# 02-USB3.net
KiCad netlist of a schematic drawn in Altium Designer
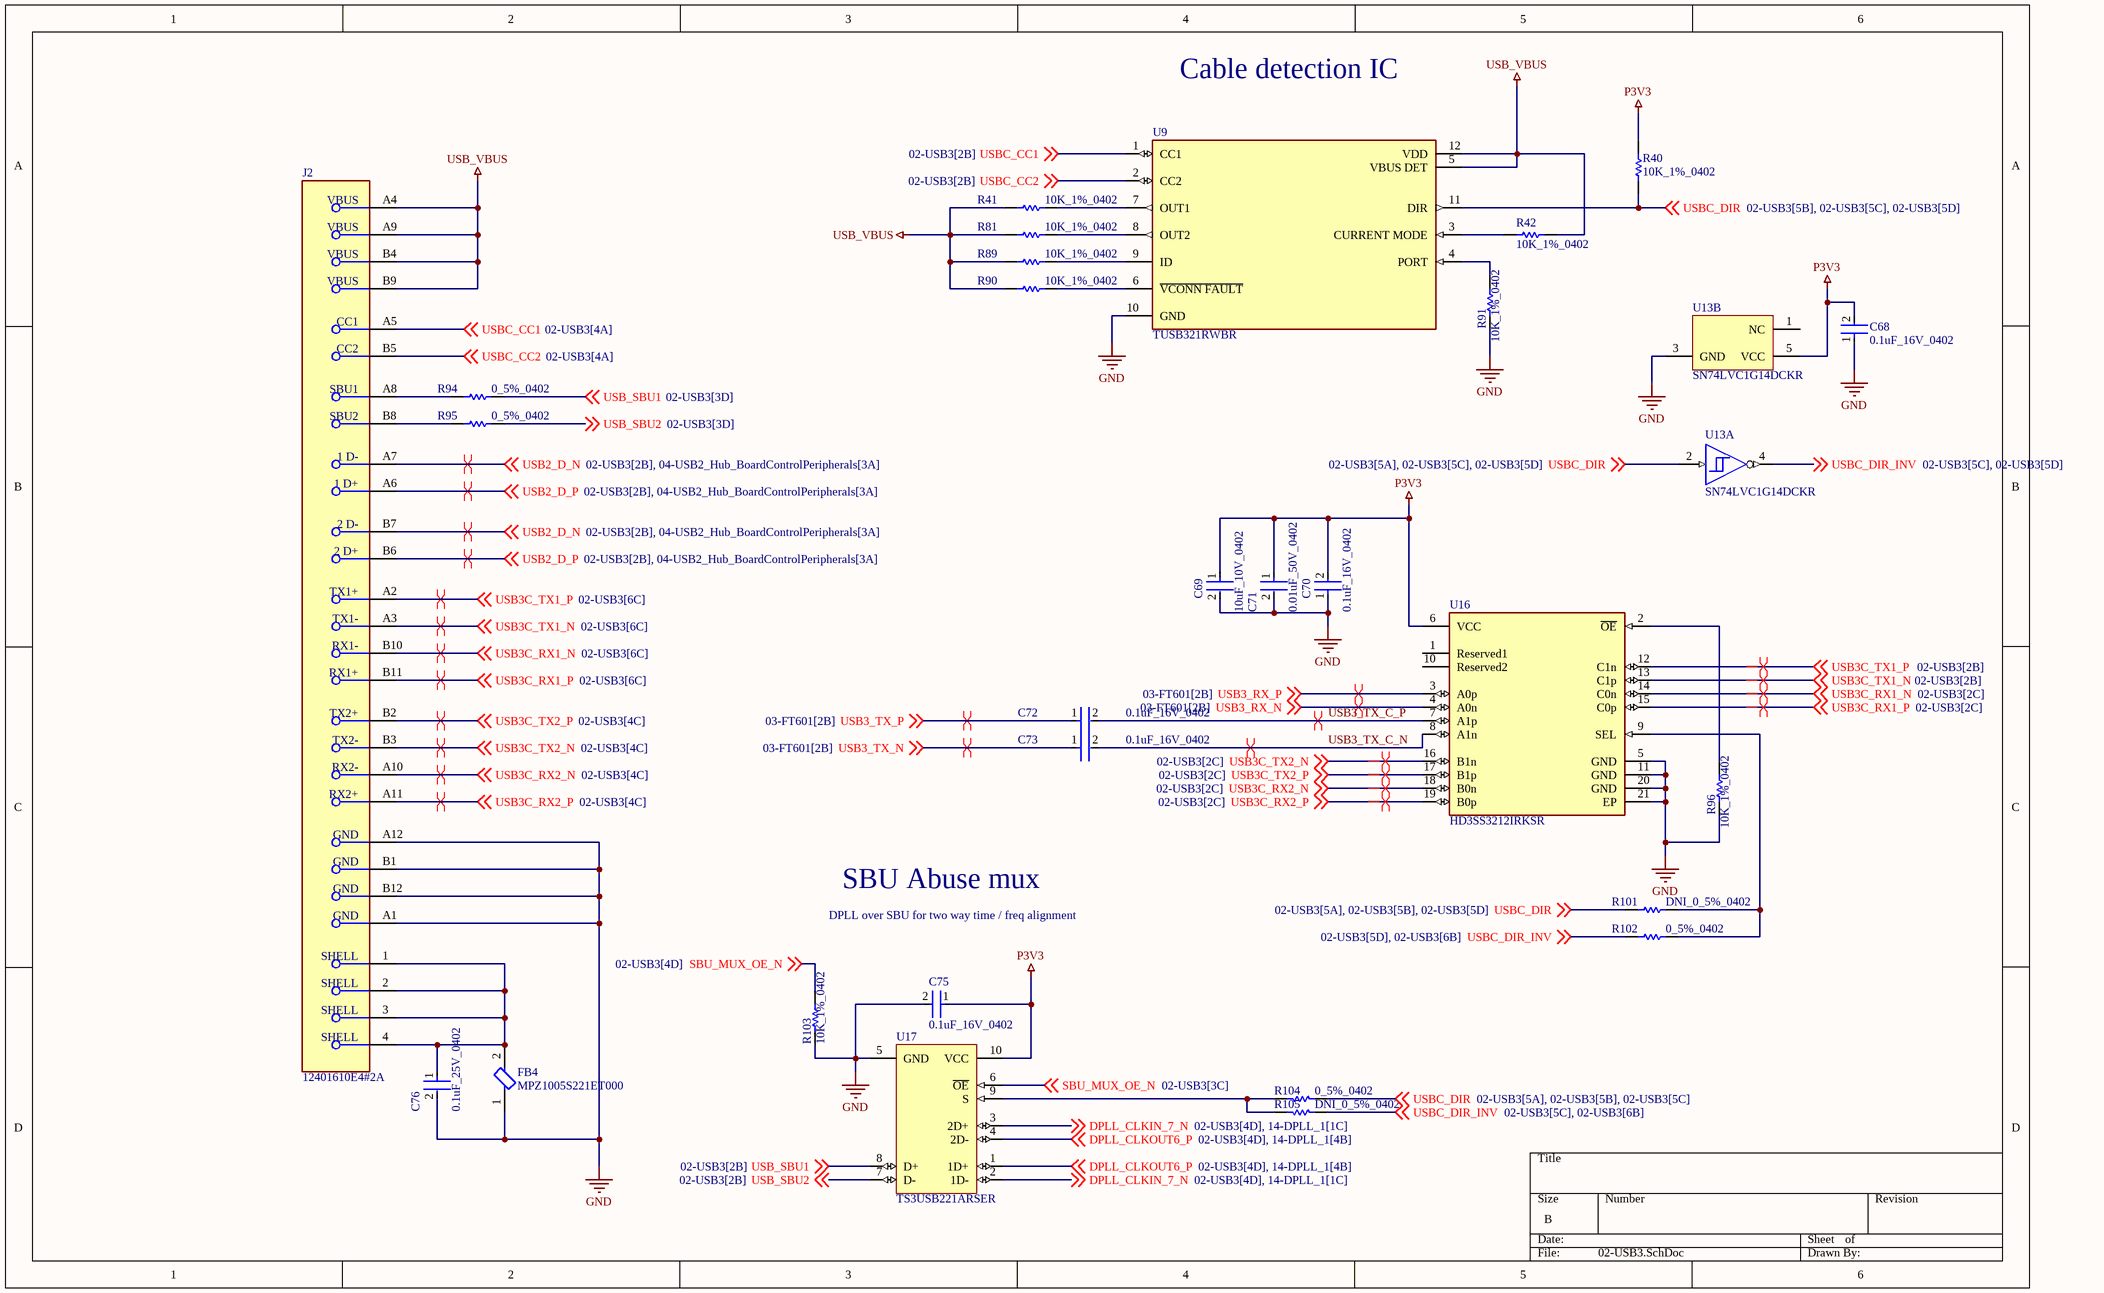
[diagram p0: 02-USB3.SchDoc]

(export (version "E")
  (design (tool "Eeschema 10.0.6"))
  (components
    (comp (ref "C68")
      (value "0.1uF_16V_0402")
      (footprint "FP-C0402-BB-MFG")
      (description "CAP CER 0.1UF 16V 5% X7R 0402")
      (fields
        (field (name "MANUFACTURER") "Kemet")
        (field (name "MANUFACTURER PART NUMBER") "C0402C104J4RACTU")
      )
      (libsource (lib "Altium Content Vault") (part "b4654b650e69147ec39a6b967a45e02"))
    )
    (comp (ref "C69")
      (value "10uF_10V_0402")
      (footprint "FP-CL05A106MP5NUNC-MFG")
      (description "CAP CER 10UF 10V X5R 0402")
      (fields
        (field (name "OCTOPART") "https://octopart.com/cl05a106mp5nunc-samsung-22457395")
        (field (name "TOLERANCE") "20%")
      )
      (libsource (lib "Altium Content Vault") (part "b4654b650e69147ec39a6b967a45e02"))
    )
    (comp (ref "C70")
      (value "0.1uF_16V_0402")
      (footprint "FP-C0402-BB-MFG")
      (description "CAP CER 0.1UF 16V 5% X7R 0402")
      (fields
        (field (name "MANUFACTURER") "Kemet")
        (field (name "MANUFACTURER PART NUMBER") "C0402C104J4RACTU")
      )
      (libsource (lib "Altium Content Vault") (part "b4654b650e69147ec39a6b967a45e02"))
    )
    (comp (ref "C71")
      (value "0.01uF_50V_0402")
      (footprint "FP-C0402-BB-MFG")
      (description "CAP CER 10000PF 50V X7R 0402")
      (fields (field (name "TOLERANCE") "0.1") (field (name "MANUFACTURER") "Kemet"))
      (libsource (lib "Altium Content Vault") (part "b4654b650e69147ec39a6b967a45e02"))
    )
    (comp (ref "C72")
      (value "0.1uF_16V_0402")
      (footprint "FP-C0402-BB-MFG")
      (description "CAP CER 0.1UF 16V 5% X7R 0402")
      (fields
        (field (name "MANUFACTURER") "Kemet")
        (field (name "MANUFACTURER PART NUMBER") "C0402C104J4RACTU")
      )
      (libsource (lib "Altium Content Vault") (part "b4654b650e69147ec39a6b967a45e02"))
    )
    (comp (ref "C73")
      (value "0.1uF_16V_0402")
      (footprint "FP-C0402-BB-MFG")
      (description "CAP CER 0.1UF 16V 5% X7R 0402")
      (fields
        (field (name "MANUFACTURER") "Kemet")
        (field (name "MANUFACTURER PART NUMBER") "C0402C104J4RACTU")
      )
      (libsource (lib "Altium Content Vault") (part "b4654b650e69147ec39a6b967a45e02"))
    )
    (comp (ref "C75")
      (value "0.1uF_16V_0402")
      (footprint "FP-C0402-BB-MFG")
      (description "CAP CER 0.1UF 16V 5% X7R 0402")
      (fields
        (field (name "MANUFACTURER") "Kemet")
        (field (name "MANUFACTURER PART NUMBER") "C0402C104J4RACTU")
      )
      (libsource (lib "Altium Content Vault") (part "b4654b650e69147ec39a6b967a45e02"))
    )
    (comp (ref "C76")
      (value "0.1uF_25V_0402")
      (footprint "FP-CGA2B-IPC_B")
      (description "Cap Ceramic 100nF 25V X7R 10% Pad SMD 0402 +125°C Automotive T/R")
      (fields (field (name "VOLTAGE") "25V") (field (name "TOLERANCE") "10%"))
      (libsource (lib "Altium Content Vault") (part "b4654b650e69147ec39a6b967a45e02"))
    )
    (comp (ref "FB4")
      (value "MPZ1005S221ET000")
      (footprint "FP-MPZ1005-IPC_A")
      (description "Power line Ferrite Bead 220Ω @ 100MHz 0.9A DCR 0.22Ω SMD 0402")
      (fields (field (name "TOLERANCE") "25%"))
      (libsource (lib "Altium Content Vault") (part "5f30dd21d616792df468990f7003faa"))
    )
    (comp (ref "J2")
      (value "12401610E4#2A")
      (footprint "FP-12401610E4#2A-MFG")
      (description "CONN RCP USB3.1 TYPEC 24P SMD RA")
      (libsource (lib "Altium Content Vault") (part "7c76f4c47d7e2af8b8797da79635f2a"))
    )
    (comp (ref "R40")
      (value "10K_1%_0402")
      (footprint "RESC1005X40X25NL10T10")
      (fields (field (name "MANUFACTURER") "Bourns") (field (name "PART NUMBER") "CR0402-FX-1002GLF"))
      (libsource (lib "Altium Content Vault") (part "RES"))
    )
    (comp (ref "R41")
      (value "10K_1%_0402")
      (footprint "RESC1005X40X25NL10T10")
      (fields (field (name "MANUFACTURER") "Bourns") (field (name "PART NUMBER") "CR0402-FX-1002GLF"))
      (libsource (lib "Altium Content Vault") (part "RES"))
    )
    (comp (ref "R42")
      (value "10K_1%_0402")
      (footprint "RESC1005X40X25NL10T10")
      (fields (field (name "MANUFACTURER") "Bourns") (field (name "PART NUMBER") "CR0402-FX-1002GLF"))
      (libsource (lib "Altium Content Vault") (part "RES"))
    )
    (comp (ref "R81")
      (value "10K_1%_0402")
      (footprint "RESC1005X40X25NL10T10")
      (fields (field (name "MANUFACTURER") "Bourns") (field (name "PART NUMBER") "CR0402-FX-1002GLF"))
      (libsource (lib "Altium Content Vault") (part "RES"))
    )
    (comp (ref "R89")
      (value "10K_1%_0402")
      (footprint "RESC1005X40X25NL10T10")
      (fields (field (name "MANUFACTURER") "Bourns") (field (name "PART NUMBER") "CR0402-FX-1002GLF"))
      (libsource (lib "Altium Content Vault") (part "RES"))
    )
    (comp (ref "R90")
      (value "10K_1%_0402")
      (footprint "RESC1005X40X25NL10T10")
      (fields (field (name "MANUFACTURER") "Bourns") (field (name "PART NUMBER") "CR0402-FX-1002GLF"))
      (libsource (lib "Altium Content Vault") (part "RES"))
    )
    (comp (ref "R91")
      (value "10K_1%_0402")
      (footprint "RESC1005X40X25NL10T10")
      (fields (field (name "MANUFACTURER") "Bourns") (field (name "PART NUMBER") "CR0402-FX-1002GLF"))
      (libsource (lib "Altium Content Vault") (part "RES"))
    )
    (comp (ref "R94")
      (value "0_5%_0402")
      (footprint "RESC1005X40X25NL05T10")
      (fields (field (name "MANUFACTURER") "Panasonic") (field (name "PART NUMBER") "ERJ-U020R00X"))
      (libsource (lib "Altium Content Vault") (part "RES"))
    )
    (comp (ref "R95")
      (value "0_5%_0402")
      (footprint "RESC1005X40X25NL05T10")
      (fields (field (name "MANUFACTURER") "Panasonic") (field (name "PART NUMBER") "ERJ-U020R00X"))
      (libsource (lib "Altium Content Vault") (part "RES"))
    )
    (comp (ref "R96")
      (value "10K_1%_0402")
      (footprint "RESC1005X40X25NL10T10")
      (fields (field (name "MANUFACTURER") "Bourns") (field (name "PART NUMBER") "CR0402-FX-1002GLF"))
      (libsource (lib "Altium Content Vault") (part "RES"))
    )
    (comp (ref "R101")
      (value "DNI_0_5%_0402")
      (footprint "RESC1005X40X25NL05T10")
      (fields (field (name "MANUFACTURER") "Panasonic") (field (name "PART NUMBER") "ERJ-U020R00X"))
      (libsource (lib "Altium Content Vault") (part "RES"))
    )
    (comp (ref "R102")
      (value "0_5%_0402")
      (footprint "RESC1005X40X25NL05T10")
      (fields (field (name "MANUFACTURER") "Panasonic") (field (name "PART NUMBER") "ERJ-U020R00X"))
      (libsource (lib "Altium Content Vault") (part "RES"))
    )
    (comp (ref "R103")
      (value "10K_1%_0402")
      (footprint "RESC1005X40X25NL10T10")
      (fields (field (name "MANUFACTURER") "Bourns") (field (name "PART NUMBER") "CR0402-FX-1002GLF"))
      (libsource (lib "Altium Content Vault") (part "RES"))
    )
    (comp (ref "R104")
      (value "0_5%_0402")
      (footprint "RESC1005X40X25NL05T10")
      (fields (field (name "MANUFACTURER") "Panasonic") (field (name "PART NUMBER") "ERJ-U020R00X"))
      (libsource (lib "Altium Content Vault") (part "RES"))
    )
    (comp (ref "R105")
      (value "DNI_0_5%_0402")
      (footprint "RESC1005X40X25NL05T10")
      (fields (field (name "MANUFACTURER") "Panasonic") (field (name "PART NUMBER") "ERJ-U020R00X"))
      (libsource (lib "Altium Content Vault") (part "RES"))
    )
    (comp (ref "U9")
      (value "TUSB321RWBR")
      (footprint "FP-RWB0012A-MFG")
      (description "IC INTERFACE SPECIALIZED 12X2QFN")
      (libsource (lib "Altium Content Vault") (part "862474eef617548c515024abf7b6d11"))
    )
    (comp (ref "U13")
      (value "SN74LVC1G14DCKR")
      (footprint "DCK0005A_L")
      (description "Single Schmitt-Trigger Inverter, DCK0005A, LARGE T&R")
      (fields
        (field (name "GENERIC PART NUMBER") "SN74LVC1G14")
        (field (name "MANUFACTURER") "Texas Instruments")
      )
      (libsource (lib "Altium Content Vault") (part "TI-SN74XXX1XX4-XX-5-SCHMITT"))
    )
    (comp (ref "U16")
      (value "HD3SS3212IRKSR")
      (footprint "FP-RKS0020A-MFG")
      (description "IC MUX 2:1 8 OHM 20VQFN")
      (libsource (lib "Altium Content Vault") (part "6af698f8cd084955c503da06e1ea90e"))
    )
    (comp (ref "U17")
      (value "TS3USB221ARSER")
      (footprint "RSE0010A_V")
      (fields (field (name "MANUFACTURER") "Texas Instruments"))
      (libsource (lib "Altium Content Vault") (part "TI-TS3USB221A-UQFN_RSE-10"))
    )
  )
  (nets
    (net (code "1") (name "/USB3_TX_C_N") (class "Default")
      (node (ref "C73") (pin "2") (pinfunction "2_2") (pintype "passive"))
      (node (ref "U16") (pin "8") (pinfunction "A1n_8") (pintype "bidirectional"))
    )
    (net (code "2") (name "/USB3_TX_C_P") (class "Default")
      (node (ref "C72") (pin "2") (pinfunction "2_2") (pintype "passive"))
      (node (ref "U16") (pin "7") (pinfunction "A1p_7") (pintype "bidirectional"))
    )
    (net (code "3") (name "DPLL_CLKIN_7_N") (class "Default")
      (node (ref "U17") (pin "2") (pinfunction "1D-_2") (pintype "bidirectional"))
      (node (ref "U17") (pin "3") (pinfunction "2D+_3") (pintype "bidirectional"))
    )
    (net (code "4") (name "DPLL_CLKOUT6_P") (class "Default")
      (node (ref "U17") (pin "1") (pinfunction "1D+_1") (pintype "bidirectional"))
      (node (ref "U17") (pin "4") (pinfunction "2D-_4") (pintype "bidirectional"))
    )
    (net (code "5") (name "GND") (class "Default")
      (node (ref "C68") (pin "1") (pinfunction "1_1") (pintype "passive"))
      (node (ref "C69") (pin "2") (pinfunction "2_2") (pintype "passive"))
      (node (ref "C70") (pin "1") (pinfunction "1_1") (pintype "passive"))
      (node (ref "C71") (pin "2") (pinfunction "2_2") (pintype "passive"))
      (node (ref "C75") (pin "2") (pinfunction "2_2") (pintype "passive"))
      (node (ref "C76") (pin "2") (pinfunction "2_2") (pintype "passive"))
      (node (ref "FB4") (pin "1") (pinfunction "1_1") (pintype "passive"))
      (node (ref "J2") (pin "A1") (pinfunction "GND_A1") (pintype "power_in"))
      (node (ref "J2") (pin "A12") (pinfunction "GND_A12") (pintype "power_in"))
      (node (ref "J2") (pin "B1") (pinfunction "GND_B1") (pintype "power_in"))
      (node (ref "J2") (pin "B12") (pinfunction "GND_B12") (pintype "power_in"))
      (node (ref "R103") (pin "2") (pinfunction "2_2") (pintype "passive"))
      (node (ref "R91") (pin "1") (pinfunction "1_1") (pintype "passive"))
      (node (ref "R96") (pin "1") (pinfunction "1_1") (pintype "passive"))
      (node (ref "U13") (pin "3") (pinfunction "GND_3") (pintype "power_in"))
      (node (ref "U16") (pin "11") (pinfunction "GND_11") (pintype "power_in"))
      (node (ref "U16") (pin "20") (pinfunction "GND_20") (pintype "power_in"))
      (node (ref "U16") (pin "21") (pinfunction "EP_21") (pintype "power_in"))
      (node (ref "U16") (pin "5") (pinfunction "GND_5") (pintype "power_in"))
      (node (ref "U17") (pin "5") (pinfunction "GND_5") (pintype "power_in"))
      (node (ref "U9") (pin "10") (pinfunction "GND_10") (pintype "power_in"))
    )
    (net (code "6") (name "Net-(C76-Pad1)") (class "Default")
      (node (ref "C76") (pin "1") (pinfunction "1_1") (pintype "passive"))
      (node (ref "FB4") (pin "2") (pinfunction "2_2") (pintype "passive"))
      (node (ref "J2") (pin "1") (pinfunction "SHELL_1") (pintype "power_in"))
      (node (ref "J2") (pin "2") (pinfunction "SHELL_2") (pintype "power_in"))
      (node (ref "J2") (pin "3") (pinfunction "SHELL_3") (pintype "power_in"))
      (node (ref "J2") (pin "4") (pinfunction "SHELL_4") (pintype "power_in"))
    )
    (net (code "7") (name "Net-(J2-SBU1)") (class "Default")
      (node (ref "J2") (pin "A8") (pinfunction "SBU1_A8") (pintype "passive"))
      (node (ref "R94") (pin "1") (pinfunction "1_1") (pintype "passive"))
    )
    (net (code "8") (name "Net-(J2-SBU2)") (class "Default")
      (node (ref "J2") (pin "B8") (pinfunction "SBU2_B8") (pintype "passive"))
      (node (ref "R95") (pin "1") (pinfunction "1_1") (pintype "passive"))
    )
    (net (code "9") (name "Net-(U9-CURRENT_MODE)") (class "Default")
      (node (ref "R42") (pin "2") (pinfunction "2_2") (pintype "passive"))
      (node (ref "U9") (pin "3") (pinfunction "CURRENT_MODE_3") (pintype "input"))
    )
    (net (code "10") (name "Net-(U9-ID)") (class "Default")
      (node (ref "R89") (pin "1") (pinfunction "1_1") (pintype "passive"))
      (node (ref "U9") (pin "9") (pinfunction "ID_9") (pintype "open_collector"))
    )
    (net (code "11") (name "Net-(U9-OUT1)") (class "Default")
      (node (ref "R41") (pin "1") (pinfunction "1_1") (pintype "passive"))
      (node (ref "U9") (pin "7") (pinfunction "OUT1_7") (pintype "output"))
    )
    (net (code "12") (name "Net-(U9-OUT2)") (class "Default")
      (node (ref "R81") (pin "1") (pinfunction "1_1") (pintype "passive"))
      (node (ref "U9") (pin "8") (pinfunction "OUT2_8") (pintype "output"))
    )
    (net (code "13") (name "Net-(U9-PORT)") (class "Default")
      (node (ref "R91") (pin "2") (pinfunction "2_2") (pintype "passive"))
      (node (ref "U9") (pin "4") (pinfunction "PORT_4") (pintype "input"))
    )
    (net (code "14") (name "Net-(U9-~{VCONN_FAULT})") (class "Default")
      (node (ref "R90") (pin "1") (pinfunction "1_1") (pintype "passive"))
      (node (ref "U9") (pin "6") (pinfunction "~{VCONN_FAULT}_6") (pintype "open_collector"))
    )
    (net (code "15") (name "Net-(U16-SEL)") (class "Default")
      (node (ref "R101") (pin "2") (pinfunction "2_2") (pintype "passive"))
      (node (ref "R102") (pin "2") (pinfunction "2_2") (pintype "passive"))
      (node (ref "U16") (pin "9") (pinfunction "SEL_9") (pintype "input"))
    )
    (net (code "16") (name "Net-(U16-~{OE})") (class "Default")
      (node (ref "R96") (pin "2") (pinfunction "2_2") (pintype "passive"))
      (node (ref "U16") (pin "2") (pinfunction "~{OE}_2") (pintype "input"))
    )
    (net (code "17") (name "Net-(U17-S)") (class "Default")
      (node (ref "R104") (pin "2") (pinfunction "2_2") (pintype "passive"))
      (node (ref "R105") (pin "2") (pinfunction "2_2") (pintype "passive"))
      (node (ref "U17") (pin "9") (pinfunction "S_9") (pintype "input"))
    )
    (net (code "18") (name "P3V3") (class "Default")
      (node (ref "C68") (pin "2") (pinfunction "2_2") (pintype "passive"))
      (node (ref "C69") (pin "1") (pinfunction "1_1") (pintype "passive"))
      (node (ref "C70") (pin "2") (pinfunction "2_2") (pintype "passive"))
      (node (ref "C71") (pin "1") (pinfunction "1_1") (pintype "passive"))
      (node (ref "C75") (pin "1") (pinfunction "1_1") (pintype "passive"))
      (node (ref "R40") (pin "1") (pinfunction "1_1") (pintype "passive"))
      (node (ref "U13") (pin "5") (pinfunction "VCC_5") (pintype "power_in"))
      (node (ref "U16") (pin "6") (pinfunction "VCC_6") (pintype "power_in"))
      (node (ref "U17") (pin "10") (pinfunction "VCC_10") (pintype "power_in"))
    )
    (net (code "19") (name "SBU_MUX_OE_N") (class "Default")
      (node (ref "R103") (pin "1") (pinfunction "1_1") (pintype "passive"))
      (node (ref "U17") (pin "6") (pinfunction "~{OE}_6") (pintype "input"))
    )
    (net (code "20") (name "USB2_D_N") (class "Default")
      (node (ref "J2") (pin "A7") (pinfunction "1_D-_A7") (pintype "passive"))
      (node (ref "J2") (pin "B7") (pinfunction "2_D-_B7") (pintype "passive"))
    )
    (net (code "21") (name "USB2_D_P") (class "Default")
      (node (ref "J2") (pin "A6") (pinfunction "1_D+_A6") (pintype "passive"))
      (node (ref "J2") (pin "B6") (pinfunction "2_D+_B6") (pintype "passive"))
    )
    (net (code "22") (name "USB3C_RX1_N") (class "Default")
      (node (ref "J2") (pin "B10") (pinfunction "RX1-_B10") (pintype "passive"))
      (node (ref "U16") (pin "14") (pinfunction "C0n_14") (pintype "bidirectional"))
    )
    (net (code "23") (name "USB3C_RX1_P") (class "Default")
      (node (ref "J2") (pin "B11") (pinfunction "RX1+_B11") (pintype "passive"))
      (node (ref "U16") (pin "15") (pinfunction "C0p_15") (pintype "bidirectional"))
    )
    (net (code "24") (name "USB3C_RX2_N") (class "Default")
      (node (ref "J2") (pin "A10") (pinfunction "RX2-_A10") (pintype "passive"))
      (node (ref "U16") (pin "18") (pinfunction "B0n_18") (pintype "bidirectional"))
    )
    (net (code "25") (name "USB3C_RX2_P") (class "Default")
      (node (ref "J2") (pin "A11") (pinfunction "RX2+_A11") (pintype "passive"))
      (node (ref "U16") (pin "19") (pinfunction "B0p_19") (pintype "bidirectional"))
    )
    (net (code "26") (name "USB3C_TX1_N") (class "Default")
      (node (ref "J2") (pin "A3") (pinfunction "TX1-_A3") (pintype "passive"))
      (node (ref "U16") (pin "13") (pinfunction "C1p_13") (pintype "bidirectional"))
    )
    (net (code "27") (name "USB3C_TX1_P") (class "Default")
      (node (ref "J2") (pin "A2") (pinfunction "TX1+_A2") (pintype "passive"))
      (node (ref "U16") (pin "12") (pinfunction "C1n_12") (pintype "bidirectional"))
    )
    (net (code "28") (name "USB3C_TX2_N") (class "Default")
      (node (ref "J2") (pin "B3") (pinfunction "TX2-_B3") (pintype "passive"))
      (node (ref "U16") (pin "16") (pinfunction "B1n_16") (pintype "bidirectional"))
    )
    (net (code "29") (name "USB3C_TX2_P") (class "Default")
      (node (ref "J2") (pin "B2") (pinfunction "TX2+_B2") (pintype "passive"))
      (node (ref "U16") (pin "17") (pinfunction "B1p_17") (pintype "bidirectional"))
    )
    (net (code "30") (name "USB3_RX_N") (class "Default")
      (node (ref "U16") (pin "4") (pinfunction "A0n_4") (pintype "bidirectional"))
    )
    (net (code "31") (name "USB3_RX_P") (class "Default")
      (node (ref "U16") (pin "3") (pinfunction "A0p_3") (pintype "bidirectional"))
    )
    (net (code "32") (name "USB3_TX_N") (class "Default")
      (node (ref "C73") (pin "1") (pinfunction "1_1") (pintype "passive"))
    )
    (net (code "33") (name "USB3_TX_P") (class "Default")
      (node (ref "C72") (pin "1") (pinfunction "1_1") (pintype "passive"))
    )
    (net (code "34") (name "USBC_CC1") (class "Default")
      (node (ref "J2") (pin "A5") (pinfunction "CC1_A5") (pintype "passive"))
      (node (ref "U9") (pin "1") (pinfunction "CC1_1") (pintype "bidirectional"))
    )
    (net (code "35") (name "USBC_CC2") (class "Default")
      (node (ref "J2") (pin "B5") (pinfunction "CC2_B5") (pintype "passive"))
      (node (ref "U9") (pin "2") (pinfunction "CC2_2") (pintype "bidirectional"))
    )
    (net (code "36") (name "USBC_DIR") (class "Default")
      (node (ref "R101") (pin "1") (pinfunction "1_1") (pintype "passive"))
      (node (ref "R104") (pin "1") (pinfunction "1_1") (pintype "passive"))
      (node (ref "R40") (pin "2") (pinfunction "2_2") (pintype "passive"))
      (node (ref "U13") (pin "2") (pinfunction "A_2") (pintype "input"))
      (node (ref "U9") (pin "11") (pinfunction "DIR_11") (pintype "output"))
    )
    (net (code "37") (name "USBC_DIR_INV") (class "Default")
      (node (ref "R102") (pin "1") (pinfunction "1_1") (pintype "passive"))
      (node (ref "R105") (pin "1") (pinfunction "1_1") (pintype "passive"))
      (node (ref "U13") (pin "4") (pinfunction "Y_4") (pintype "output"))
    )
    (net (code "38") (name "USB_SBU1") (class "Default")
      (node (ref "R94") (pin "2") (pinfunction "2_2") (pintype "passive"))
      (node (ref "U17") (pin "8") (pinfunction "D+_8") (pintype "bidirectional"))
    )
    (net (code "39") (name "USB_SBU2") (class "Default")
      (node (ref "R95") (pin "2") (pinfunction "2_2") (pintype "passive"))
      (node (ref "U17") (pin "7") (pinfunction "D-_7") (pintype "bidirectional"))
    )
    (net (code "40") (name "USB_VBUS") (class "Default")
      (node (ref "J2") (pin "A4") (pinfunction "VBUS_A4") (pintype "power_in"))
      (node (ref "J2") (pin "A9") (pinfunction "VBUS_A9") (pintype "power_in"))
      (node (ref "J2") (pin "B4") (pinfunction "VBUS_B4") (pintype "power_in"))
      (node (ref "J2") (pin "B9") (pinfunction "VBUS_B9") (pintype "power_in"))
      (node (ref "R41") (pin "2") (pinfunction "2_2") (pintype "passive"))
      (node (ref "R42") (pin "1") (pinfunction "1_1") (pintype "passive"))
      (node (ref "R81") (pin "2") (pinfunction "2_2") (pintype "passive"))
      (node (ref "R89") (pin "2") (pinfunction "2_2") (pintype "passive"))
      (node (ref "R90") (pin "2") (pinfunction "2_2") (pintype "passive"))
      (node (ref "U9") (pin "12") (pinfunction "VDD_12") (pintype "power_in"))
      (node (ref "U9") (pin "5") (pinfunction "VBUS_DET_5") (pintype "power_in"))
    )
    (net (code "41") (name "unconnected-(U13B-NC-Pad1)") (class "Default")
      (node (ref "U13") (pin "1") (pinfunction "NC_1") (pintype "passive"))
    )
    (net (code "42") (name "unconnected-(U16-Reserved1-Pad1)") (class "Default")
      (node (ref "U16") (pin "1") (pinfunction "Reserved1_1") (pintype "passive"))
    )
    (net (code "43") (name "unconnected-(U16-Reserved2-Pad10)") (class "Default")
      (node (ref "U16") (pin "10") (pinfunction "Reserved2_10") (pintype "passive"))
    )
  )
)
